# CANFD.net
KiCad netlist of a schematic drawn in Altium Designer
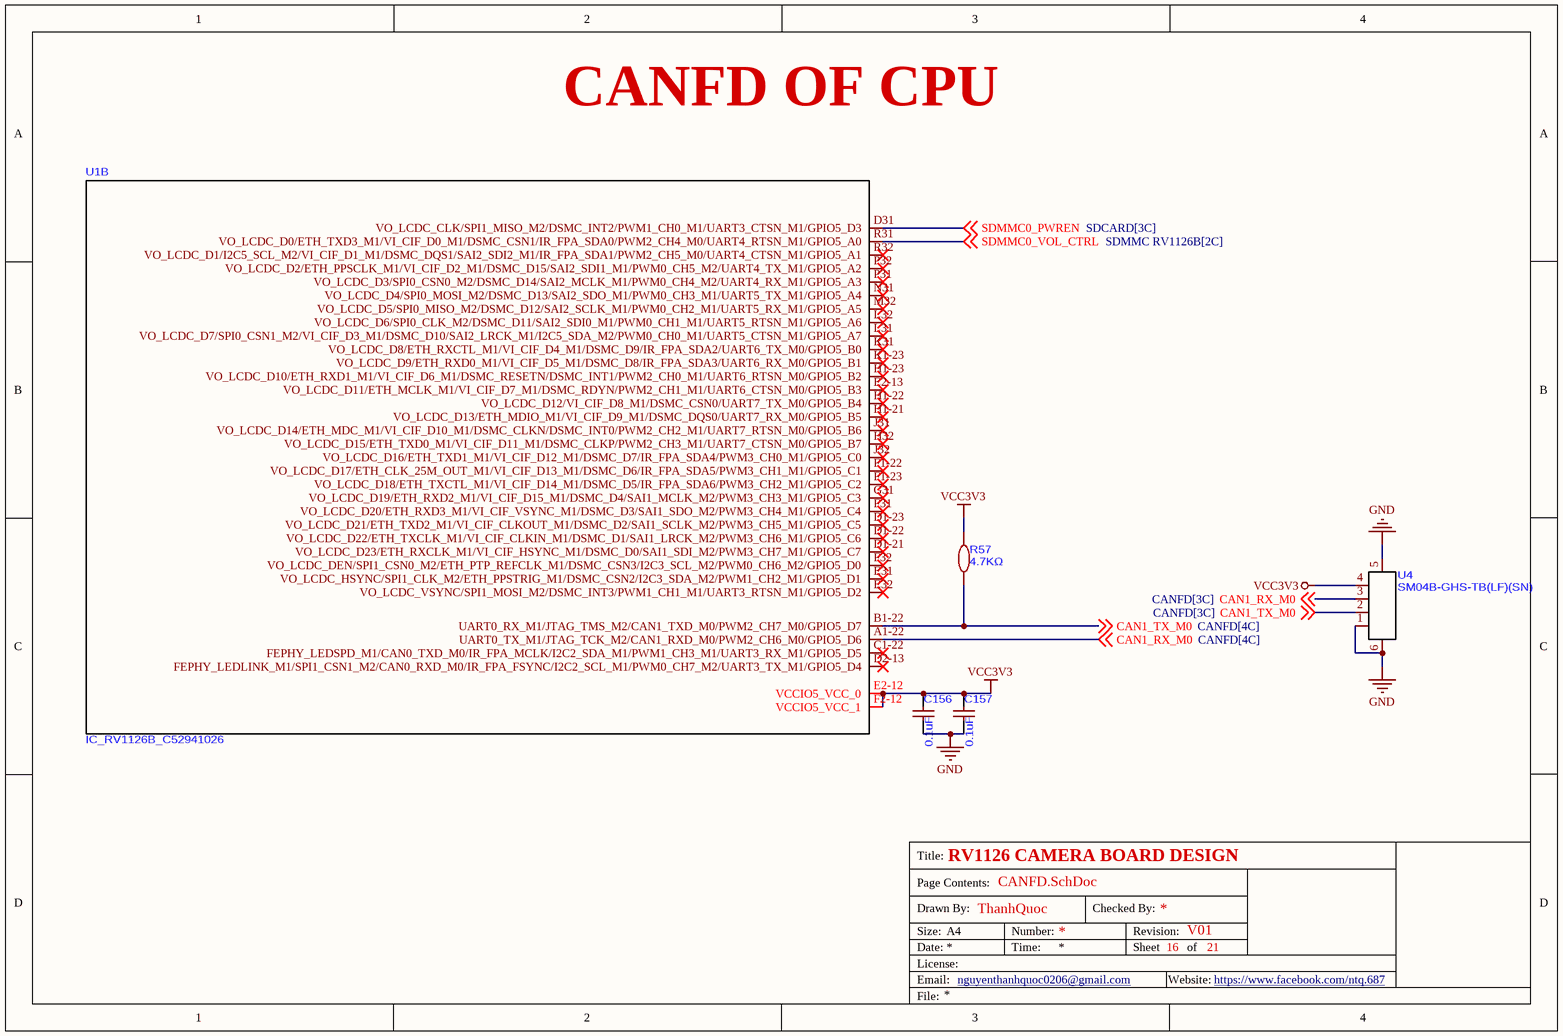
[diagram p0: CANFD.SchDoc]

(export (version "E")
  (design (tool "Eeschema 10.0.6"))
  (components
    (comp (ref "C156")
      (value "0.1uF")
      (footprint "C0201")
      (description "0.1uF ±10% 6.3V Ceramic Capacitor X5R 0201")
      (libsource (lib "Schlib1") (part "CAP_100nF-6.3V-10%-0201_1"))
    )
    (comp (ref "C157")
      (value "0.1uF")
      (footprint "C0201")
      (description "0.1uF ±10% 6.3V Ceramic Capacitor X5R 0201")
      (libsource (lib "Schlib1") (part "CAP_100nF-6.3V-10%-0201_1"))
    )
    (comp (ref "R57")
      (value "4.7KΩ")
      (footprint "R0201")
      (description "RES 4.7kΩ ±1% 50mW 0201")
      (libsource (lib "Schlib1") (part "RES_4.7K-50mW-1%-0201"))
    )
    (comp (ref "U1")
      (value "IC_RV1126B_C52941026")
      (footprint "CCSP-491_L14.0-W14.0-TL_RV1126B")
      (libsource (lib "Schlib1") (part "IC_RV1126B_C52941026"))
    )
    (comp (ref "U4")
      (value "SM04B-GHS-TB(LF)(SN)")
      (footprint "CONN-SMD_4P-P1.25_SM04B-GHS-TB-LF-SN")
      (description "CONN HEADER SMD R/A 4POS 1.25mm")
      (libsource (lib "Schlib1") (part "SM04B-GHS-TB(LF)(SN)"))
    )
  )
  (nets
    (net (code "1") (name "CAN1_RX_M0") (class "Default")
      (node (ref "U1") (pin "A1-22") (pinfunction "UART0_TX_M1/JTAG_TCK_M2/CAN1_RXD_M0/PWM2_CH6_M0/GPIO5_D6_A1-22") (pintype "passive"))
      (node (ref "U4") (pin "3") (pinfunction "3_3") (pintype "passive"))
    )
    (net (code "2") (name "CAN1_TX_M0") (class "Default")
      (node (ref "R57") (pin "1") (pinfunction "1_1") (pintype "passive"))
      (node (ref "U1") (pin "B1-22") (pinfunction "UART0_RX_M1/JTAG_TMS_M2/CAN1_TXD_M0/PWM2_CH7_M0/GPIO5_D7_B1-22") (pintype "passive"))
      (node (ref "U4") (pin "2") (pinfunction "2_2") (pintype "passive"))
    )
    (net (code "3") (name "GND") (class "Default")
      (node (ref "C156") (pin "1") (pinfunction "1_1") (pintype "passive"))
      (node (ref "C157") (pin "1") (pinfunction "1_1") (pintype "passive"))
      (node (ref "U4") (pin "1") (pinfunction "1_1") (pintype "passive"))
      (node (ref "U4") (pin "5") (pinfunction "5_5") (pintype "passive"))
      (node (ref "U4") (pin "6") (pinfunction "6_6") (pintype "passive"))
    )
    (net (code "4") (name "SDMMC0_PWREN") (class "Default")
      (node (ref "U1") (pin "D31") (pinfunction "VO_LCDC_CLK/SPI1_MISO_M2/DSMC_INT2/PWM1_CH0_M1/UART3_CTSN_M1/GPIO5_D3_D31") (pintype "passive"))
    )
    (net (code "5") (name "SDMMC0_VOL_CTRL") (class "Default")
      (node (ref "U1") (pin "R31") (pinfunction "VO_LCDC_D0/ETH_TXD3_M1/VI_CIF_D0_M1/DSMC_CSN1/IR_FPA_SDA0/PWM2_CH4_M0/UART4_RTSN_M1/GPIO5_A0_R31") (pintype "passive"))
    )
    (net (code "6") (name "VCC3V3") (class "Default")
      (node (ref "C156") (pin "2") (pinfunction "2_2") (pintype "passive"))
      (node (ref "C157") (pin "2") (pinfunction "2_2") (pintype "passive"))
      (node (ref "R57") (pin "2") (pinfunction "2_2") (pintype "passive"))
      (node (ref "U1") (pin "E2-12") (pinfunction "VCCIO5_VCC_0_E2-12") (pintype "passive"))
      (node (ref "U1") (pin "F2-12") (pinfunction "VCCIO5_VCC_1_F2-12") (pintype "passive"))
      (node (ref "U4") (pin "4") (pinfunction "4_4") (pintype "passive"))
    )
    (net (code "7") (name "unconnected-(U1B-FEPHY_LEDLINK_M1{slash}SPI1_CSN1_M2{slash}CAN0_RXD_M0{slash}IR_FPA_FSYNC{slash}I2C2_SCL_M1{slash}PWM0_CH7_M2{slash}UART3_TX_M1{slash}GPIO5_D4-PadD2-13)") (class "Default")
      (node (ref "U1") (pin "D2-13") (pinfunction "FEPHY_LEDLINK_M1/SPI1_CSN1_M2/CAN0_RXD_M0/IR_FPA_FSYNC/I2C2_SCL_M1/PWM0_CH7_M2/UART3_TX_M1/GPIO5_D4_D2-13") (pintype "passive+no_connect"))
    )
    (net (code "8") (name "unconnected-(U1B-FEPHY_LEDSPD_M1{slash}CAN0_TXD_M0{slash}IR_FPA_MCLK{slash}I2C2_SDA_M1{slash}PWM1_CH3_M1{slash}UART3_RX_M1{slash}GPIO5_D5-PadC1-22)") (class "Default")
      (node (ref "U1") (pin "C1-22") (pinfunction "FEPHY_LEDSPD_M1/CAN0_TXD_M0/IR_FPA_MCLK/I2C2_SDA_M1/PWM1_CH3_M1/UART3_RX_M1/GPIO5_D5_C1-22") (pintype "passive+no_connect"))
    )
    (net (code "9") (name "unconnected-(U1B-VO_LCDC_D1{slash}I2C5_SCL_M2{slash}VI_CIF_D1_M1{slash}DSMC_DQS1{slash}SAI2_SDI2_M1{slash}IR_FPA_SDA1{slash}PWM2_CH5_M0{slash}UART4_CTSN_M1{slash}GPIO5_A1-PadR32)") (class "Default")
      (node (ref "U1") (pin "R32") (pinfunction "VO_LCDC_D1/I2C5_SCL_M2/VI_CIF_D1_M1/DSMC_DQS1/SAI2_SDI2_M1/IR_FPA_SDA1/PWM2_CH5_M0/UART4_CTSN_M1/GPIO5_A1_R32") (pintype "passive+no_connect"))
    )
    (net (code "10") (name "unconnected-(U1B-VO_LCDC_D2{slash}ETH_PPSCLK_M1{slash}VI_CIF_D2_M1{slash}DSMC_D15{slash}SAI2_SDI1_M1{slash}PWM0_CH5_M2{slash}UART4_TX_M1{slash}GPIO5_A2-PadP32)") (class "Default")
      (node (ref "U1") (pin "P32") (pinfunction "VO_LCDC_D2/ETH_PPSCLK_M1/VI_CIF_D2_M1/DSMC_D15/SAI2_SDI1_M1/PWM0_CH5_M2/UART4_TX_M1/GPIO5_A2_P32") (pintype "passive+no_connect"))
    )
    (net (code "11") (name "unconnected-(U1B-VO_LCDC_D3{slash}SPI0_CSN0_M2{slash}DSMC_D14{slash}SAI2_MCLK_M1{slash}PWM0_CH4_M2{slash}UART4_RX_M1{slash}GPIO5_A3-PadP31)") (class "Default")
      (node (ref "U1") (pin "P31") (pinfunction "VO_LCDC_D3/SPI0_CSN0_M2/DSMC_D14/SAI2_MCLK_M1/PWM0_CH4_M2/UART4_RX_M1/GPIO5_A3_P31") (pintype "passive+no_connect"))
    )
    (net (code "12") (name "unconnected-(U1B-VO_LCDC_D4{slash}SPI0_MOSI_M2{slash}DSMC_D13{slash}SAI2_SDO_M1{slash}PWM0_CH3_M1{slash}UART5_TX_M1{slash}GPIO5_A4-PadN31)") (class "Default")
      (node (ref "U1") (pin "N31") (pinfunction "VO_LCDC_D4/SPI0_MOSI_M2/DSMC_D13/SAI2_SDO_M1/PWM0_CH3_M1/UART5_TX_M1/GPIO5_A4_N31") (pintype "passive+no_connect"))
    )
    (net (code "13") (name "unconnected-(U1B-VO_LCDC_D5{slash}SPI0_MISO_M2{slash}DSMC_D12{slash}SAI2_SCLK_M1{slash}PWM0_CH2_M1{slash}UART5_RX_M1{slash}GPIO5_A5-PadM32)") (class "Default")
      (node (ref "U1") (pin "M32") (pinfunction "VO_LCDC_D5/SPI0_MISO_M2/DSMC_D12/SAI2_SCLK_M1/PWM0_CH2_M1/UART5_RX_M1/GPIO5_A5_M32") (pintype "passive+no_connect"))
    )
    (net (code "14") (name "unconnected-(U1B-VO_LCDC_D6{slash}SPI0_CLK_M2{slash}DSMC_D11{slash}SAI2_SDI0_M1{slash}PWM0_CH1_M1{slash}UART5_RTSN_M1{slash}GPIO5_A6-PadL32)") (class "Default")
      (node (ref "U1") (pin "L32") (pinfunction "VO_LCDC_D6/SPI0_CLK_M2/DSMC_D11/SAI2_SDI0_M1/PWM0_CH1_M1/UART5_RTSN_M1/GPIO5_A6_L32") (pintype "passive+no_connect"))
    )
    (net (code "15") (name "unconnected-(U1B-VO_LCDC_D7{slash}SPI0_CSN1_M2{slash}VI_CIF_D3_M1{slash}DSMC_D10{slash}SAI2_LRCK_M1{slash}I2C5_SDA_M2{slash}PWM0_CH0_M1{slash}UART5_CTSN_M1{slash}GPIO5_A7-PadL31)") (class "Default")
      (node (ref "U1") (pin "L31") (pinfunction "VO_LCDC_D7/SPI0_CSN1_M2/VI_CIF_D3_M1/DSMC_D10/SAI2_LRCK_M1/I2C5_SDA_M2/PWM0_CH0_M1/UART5_CTSN_M1/GPIO5_A7_L31") (pintype "passive+no_connect"))
    )
    (net (code "16") (name "unconnected-(U1B-VO_LCDC_D8{slash}ETH_RXCTL_M1{slash}VI_CIF_D4_M1{slash}DSMC_D9{slash}IR_FPA_SDA2{slash}UART6_TX_M0{slash}GPIO5_B0-PadK31)") (class "Default")
      (node (ref "U1") (pin "K31") (pinfunction "VO_LCDC_D8/ETH_RXCTL_M1/VI_CIF_D4_M1/DSMC_D9/IR_FPA_SDA2/UART6_TX_M0/GPIO5_B0_K31") (pintype "passive+no_connect"))
    )
    (net (code "17") (name "unconnected-(U1B-VO_LCDC_D9{slash}ETH_RXD0_M1{slash}VI_CIF_D5_M1{slash}DSMC_D8{slash}IR_FPA_SDA3{slash}UART6_RX_M0{slash}GPIO5_B1-PadK1-23)") (class "Default")
      (node (ref "U1") (pin "K1-23") (pinfunction "VO_LCDC_D9/ETH_RXD0_M1/VI_CIF_D5_M1/DSMC_D8/IR_FPA_SDA3/UART6_RX_M0/GPIO5_B1_K1-23") (pintype "passive+no_connect"))
    )
    (net (code "18") (name "unconnected-(U1B-VO_LCDC_D10{slash}ETH_RXD1_M1{slash}VI_CIF_D6_M1{slash}DSMC_RESETN{slash}DSMC_INT1{slash}PWM2_CH0_M1{slash}UART6_RTSN_M0{slash}GPIO5_B2-PadH1-23)") (class "Default")
      (node (ref "U1") (pin "H1-23") (pinfunction "VO_LCDC_D10/ETH_RXD1_M1/VI_CIF_D6_M1/DSMC_RESETN/DSMC_INT1/PWM2_CH0_M1/UART6_RTSN_M0/GPIO5_B2_H1-23") (pintype "passive+no_connect"))
    )
    (net (code "19") (name "unconnected-(U1B-VO_LCDC_D11{slash}ETH_MCLK_M1{slash}VI_CIF_D7_M1{slash}DSMC_RDYN{slash}PWM2_CH1_M1{slash}UART6_CTSN_M0{slash}GPIO5_B3-PadE2-13)") (class "Default")
      (node (ref "U1") (pin "E2-13") (pinfunction "VO_LCDC_D11/ETH_MCLK_M1/VI_CIF_D7_M1/DSMC_RDYN/PWM2_CH1_M1/UART6_CTSN_M0/GPIO5_B3_E2-13") (pintype "passive+no_connect"))
    )
    (net (code "20") (name "unconnected-(U1B-VO_LCDC_D12{slash}VI_CIF_D8_M1{slash}DSMC_CSN0{slash}UART7_TX_M0{slash}GPIO5_B4-PadH1-22)") (class "Default")
      (node (ref "U1") (pin "H1-22") (pinfunction "VO_LCDC_D12/VI_CIF_D8_M1/DSMC_CSN0/UART7_TX_M0/GPIO5_B4_H1-22") (pintype "passive+no_connect"))
    )
    (net (code "21") (name "unconnected-(U1B-VO_LCDC_D13{slash}ETH_MDIO_M1{slash}VI_CIF_D9_M1{slash}DSMC_DQS0{slash}UART7_RX_M0{slash}GPIO5_B5-PadH1-21)") (class "Default")
      (node (ref "U1") (pin "H1-21") (pinfunction "VO_LCDC_D13/ETH_MDIO_M1/VI_CIF_D9_M1/DSMC_DQS0/UART7_RX_M0/GPIO5_B5_H1-21") (pintype "passive+no_connect"))
    )
    (net (code "22") (name "unconnected-(U1B-VO_LCDC_D14{slash}ETH_MDC_M1{slash}VI_CIF_D10_M1{slash}DSMC_CLKN{slash}DSMC_INT0{slash}PWM2_CH2_M1{slash}UART7_RTSN_M0{slash}GPIO5_B6-PadJ31)") (class "Default")
      (node (ref "U1") (pin "J31") (pinfunction "VO_LCDC_D14/ETH_MDC_M1/VI_CIF_D10_M1/DSMC_CLKN/DSMC_INT0/PWM2_CH2_M1/UART7_RTSN_M0/GPIO5_B6_J31") (pintype "passive+no_connect"))
    )
    (net (code "23") (name "unconnected-(U1B-VO_LCDC_D15{slash}ETH_TXD0_M1{slash}VI_CIF_D11_M1{slash}DSMC_CLKP{slash}PWM2_CH3_M1{slash}UART7_CTSN_M0{slash}GPIO5_B7-PadH32)") (class "Default")
      (node (ref "U1") (pin "H32") (pinfunction "VO_LCDC_D15/ETH_TXD0_M1/VI_CIF_D11_M1/DSMC_CLKP/PWM2_CH3_M1/UART7_CTSN_M0/GPIO5_B7_H32") (pintype "passive+no_connect"))
    )
    (net (code "24") (name "unconnected-(U1B-VO_LCDC_D16{slash}ETH_TXD1_M1{slash}VI_CIF_D12_M1{slash}DSMC_D7{slash}IR_FPA_SDA4{slash}PWM3_CH0_M1{slash}GPIO5_C0-PadJ32)") (class "Default")
      (node (ref "U1") (pin "J32") (pinfunction "VO_LCDC_D16/ETH_TXD1_M1/VI_CIF_D12_M1/DSMC_D7/IR_FPA_SDA4/PWM3_CH0_M1/GPIO5_C0_J32") (pintype "passive+no_connect"))
    )
    (net (code "25") (name "unconnected-(U1B-VO_LCDC_D17{slash}ETH_CLK_25M_OUT_M1{slash}VI_CIF_D13_M1{slash}DSMC_D6{slash}IR_FPA_SDA5{slash}PWM3_CH1_M1{slash}GPIO5_C1-PadF1-22)") (class "Default")
      (node (ref "U1") (pin "F1-22") (pinfunction "VO_LCDC_D17/ETH_CLK_25M_OUT_M1/VI_CIF_D13_M1/DSMC_D6/IR_FPA_SDA5/PWM3_CH1_M1/GPIO5_C1_F1-22") (pintype "passive+no_connect"))
    )
    (net (code "26") (name "unconnected-(U1B-VO_LCDC_D18{slash}ETH_TXCTL_M1{slash}VI_CIF_D14_M1{slash}DSMC_D5{slash}IR_FPA_SDA6{slash}PWM3_CH2_M1{slash}GPIO5_C2-PadF1-23)") (class "Default")
      (node (ref "U1") (pin "F1-23") (pinfunction "VO_LCDC_D18/ETH_TXCTL_M1/VI_CIF_D14_M1/DSMC_D5/IR_FPA_SDA6/PWM3_CH2_M1/GPIO5_C2_F1-23") (pintype "passive+no_connect"))
    )
    (net (code "27") (name "unconnected-(U1B-VO_LCDC_D19{slash}ETH_RXD2_M1{slash}VI_CIF_D15_M1{slash}DSMC_D4{slash}SAI1_MCLK_M2{slash}PWM3_CH3_M1{slash}GPIO5_C3-PadG31)") (class "Default")
      (node (ref "U1") (pin "G31") (pinfunction "VO_LCDC_D19/ETH_RXD2_M1/VI_CIF_D15_M1/DSMC_D4/SAI1_MCLK_M2/PWM3_CH3_M1/GPIO5_C3_G31") (pintype "passive+no_connect"))
    )
    (net (code "28") (name "unconnected-(U1B-VO_LCDC_D20{slash}ETH_RXD3_M1{slash}VI_CIF_VSYNC_M1{slash}DSMC_D3{slash}SAI1_SDO_M2{slash}PWM3_CH4_M1{slash}GPIO5_C4-PadF31)") (class "Default")
      (node (ref "U1") (pin "F31") (pinfunction "VO_LCDC_D20/ETH_RXD3_M1/VI_CIF_VSYNC_M1/DSMC_D3/SAI1_SDO_M2/PWM3_CH4_M1/GPIO5_C4_F31") (pintype "passive+no_connect"))
    )
    (net (code "29") (name "unconnected-(U1B-VO_LCDC_D21{slash}ETH_TXD2_M1{slash}VI_CIF_CLKOUT_M1{slash}DSMC_D2{slash}SAI1_SCLK_M2{slash}PWM3_CH5_M1{slash}GPIO5_C5-PadD1-23)") (class "Default")
      (node (ref "U1") (pin "D1-23") (pinfunction "VO_LCDC_D21/ETH_TXD2_M1/VI_CIF_CLKOUT_M1/DSMC_D2/SAI1_SCLK_M2/PWM3_CH5_M1/GPIO5_C5_D1-23") (pintype "passive+no_connect"))
    )
    (net (code "30") (name "unconnected-(U1B-VO_LCDC_D22{slash}ETH_TXCLK_M1{slash}VI_CIF_CLKIN_M1{slash}DSMC_D1{slash}SAI1_LRCK_M2{slash}PWM3_CH6_M1{slash}GPIO5_C6-PadD1-22)") (class "Default")
      (node (ref "U1") (pin "D1-22") (pinfunction "VO_LCDC_D22/ETH_TXCLK_M1/VI_CIF_CLKIN_M1/DSMC_D1/SAI1_LRCK_M2/PWM3_CH6_M1/GPIO5_C6_D1-22") (pintype "passive+no_connect"))
    )
    (net (code "31") (name "unconnected-(U1B-VO_LCDC_D23{slash}ETH_RXCLK_M1{slash}VI_CIF_HSYNC_M1{slash}DSMC_D0{slash}SAI1_SDI_M2{slash}PWM3_CH7_M1{slash}GPIO5_C7-PadD1-21)") (class "Default")
      (node (ref "U1") (pin "D1-21") (pinfunction "VO_LCDC_D23/ETH_RXCLK_M1/VI_CIF_HSYNC_M1/DSMC_D0/SAI1_SDI_M2/PWM3_CH7_M1/GPIO5_C7_D1-21") (pintype "passive+no_connect"))
    )
    (net (code "32") (name "unconnected-(U1B-VO_LCDC_DEN{slash}SPI1_CSN0_M2{slash}ETH_PTP_REFCLK_M1{slash}DSMC_CSN3{slash}I2C3_SCL_M2{slash}PWM0_CH6_M2{slash}GPIO5_D0-PadF32)") (class "Default")
      (node (ref "U1") (pin "F32") (pinfunction "VO_LCDC_DEN/SPI1_CSN0_M2/ETH_PTP_REFCLK_M1/DSMC_CSN3/I2C3_SCL_M2/PWM0_CH6_M2/GPIO5_D0_F32") (pintype "passive+no_connect"))
    )
    (net (code "33") (name "unconnected-(U1B-VO_LCDC_HSYNC{slash}SPI1_CLK_M2{slash}ETH_PPSTRIG_M1{slash}DSMC_CSN2{slash}I2C3_SDA_M2{slash}PWM1_CH2_M1{slash}GPIO5_D1-PadE31)") (class "Default")
      (node (ref "U1") (pin "E31") (pinfunction "VO_LCDC_HSYNC/SPI1_CLK_M2/ETH_PPSTRIG_M1/DSMC_CSN2/I2C3_SDA_M2/PWM1_CH2_M1/GPIO5_D1_E31") (pintype "passive+no_connect"))
    )
    (net (code "34") (name "unconnected-(U1B-VO_LCDC_VSYNC{slash}SPI1_MOSI_M2{slash}DSMC_INT3{slash}PWM1_CH1_M1{slash}UART3_RTSN_M1{slash}GPIO5_D2-PadE32)") (class "Default")
      (node (ref "U1") (pin "E32") (pinfunction "VO_LCDC_VSYNC/SPI1_MOSI_M2/DSMC_INT3/PWM1_CH1_M1/UART3_RTSN_M1/GPIO5_D2_E32") (pintype "passive+no_connect"))
    )
  )
)
